# Sensors.net
KiCad netlist of a schematic drawn in Altium Designer
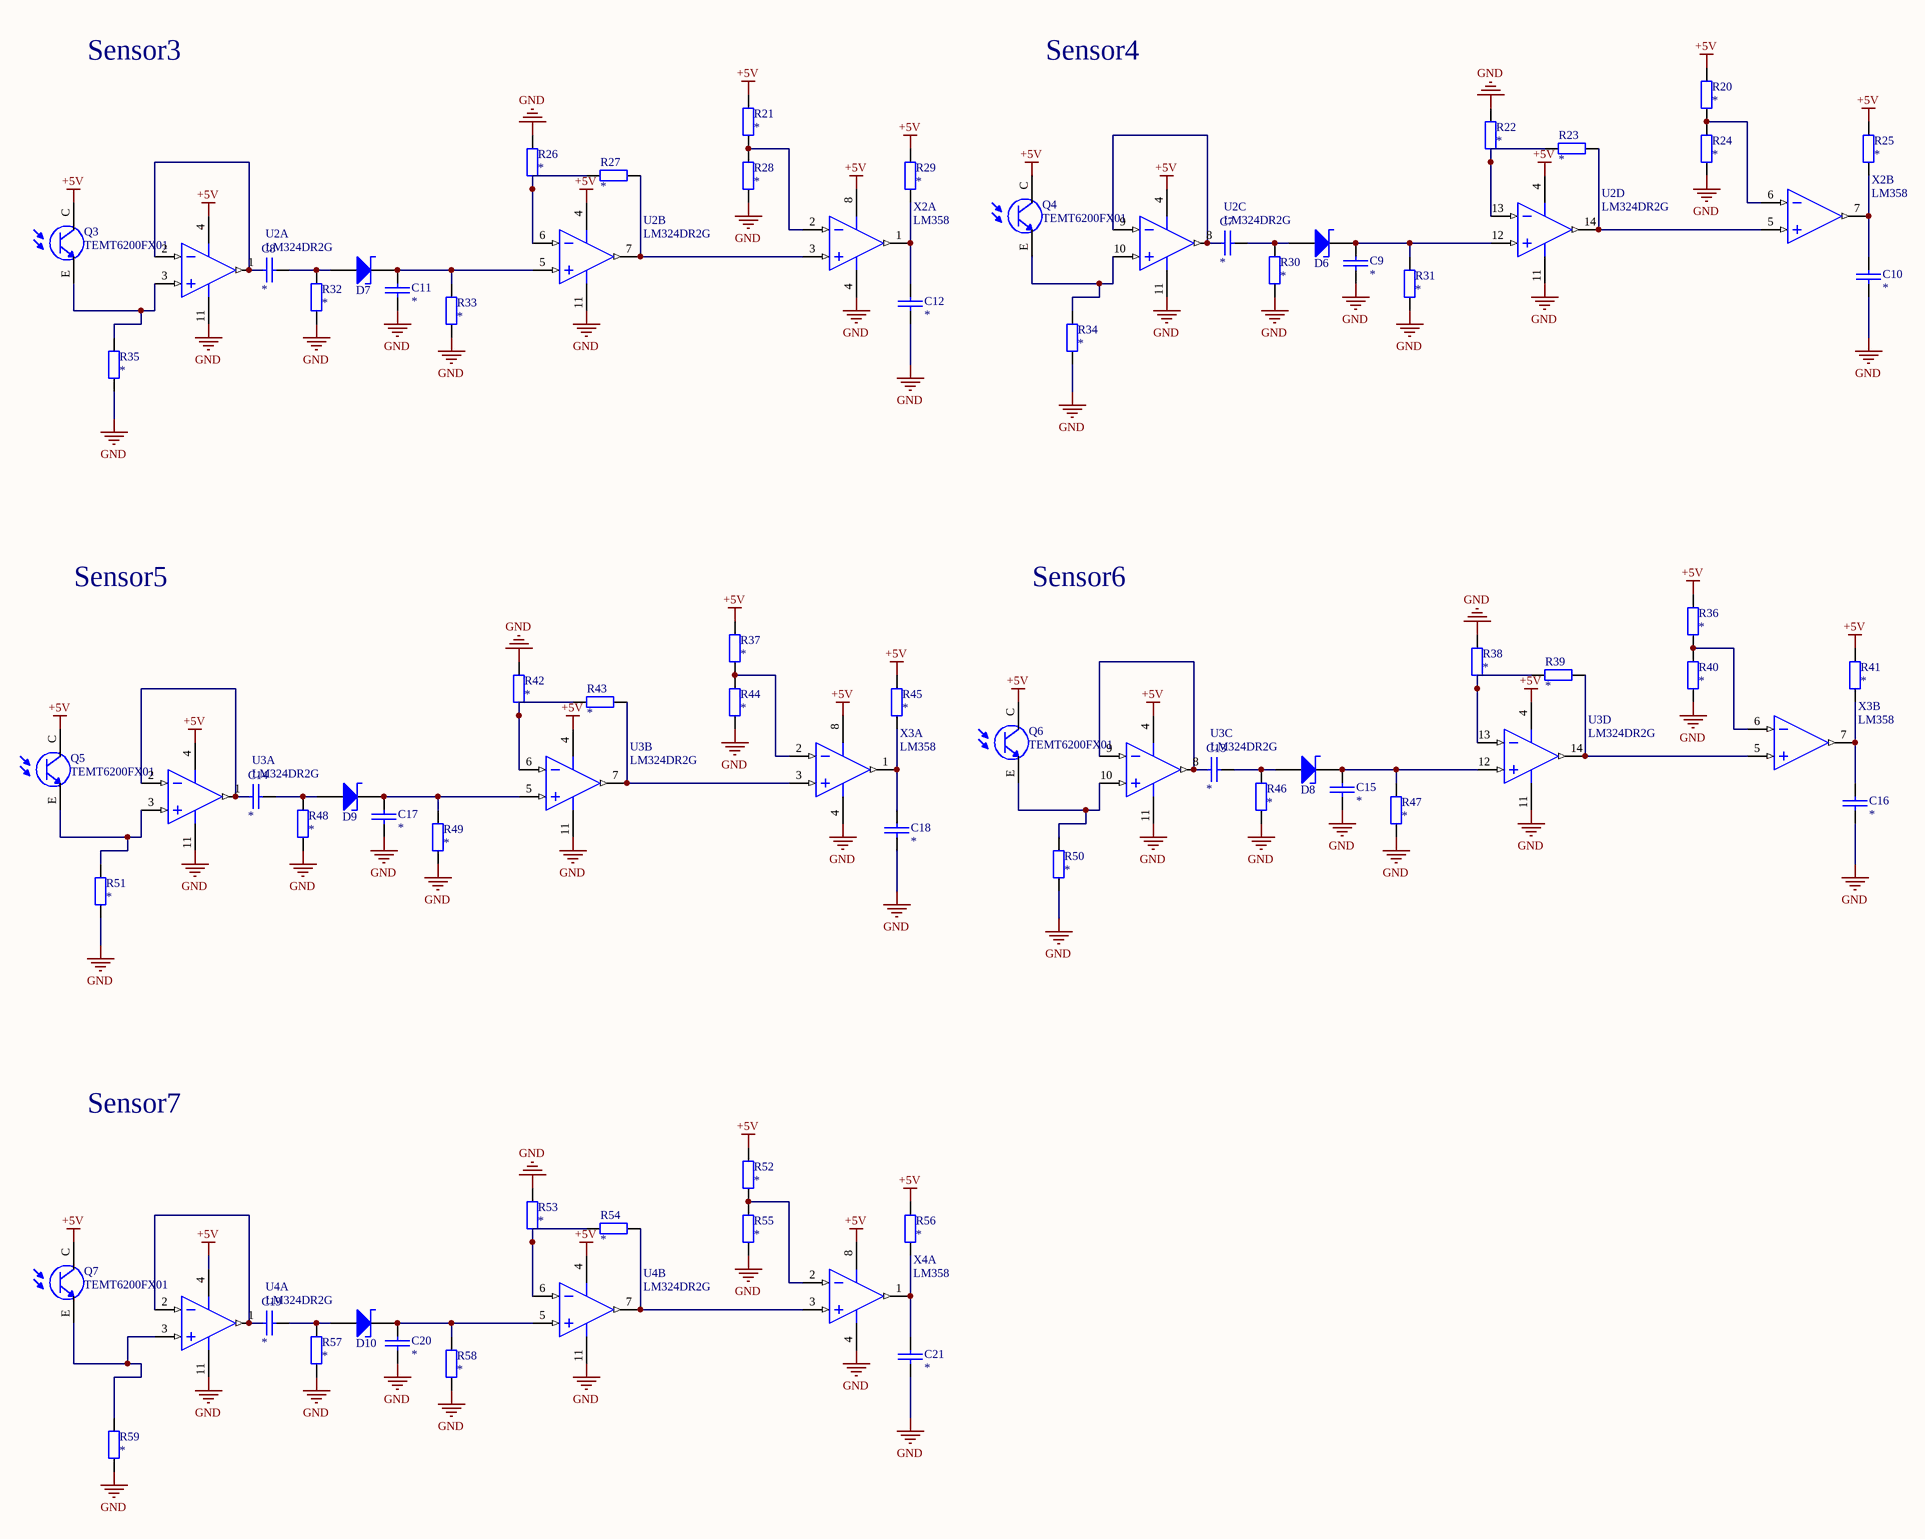
[diagram p0: Sensors.SchDoc]

(export (version "E")
  (design (tool "Eeschema 10.0.6"))
  (components
    (comp (ref "C7")
      (value "*")
      (footprint "0805 CAP")
      (description "SMT ceramic capacitor 0805 size")
      (libsource (lib "EE209_Library") (part "CerCap_SMT_0805"))
    )
    (comp (ref "C8")
      (value "*")
      (footprint "0805 CAP")
      (description "SMT ceramic capacitor 0805 size")
      (libsource (lib "EE209_Library") (part "CerCap_SMT_0805"))
    )
    (comp (ref "C9")
      (value "*")
      (footprint "0805 CAP")
      (description "SMT ceramic capacitor 0805 size")
      (libsource (lib "EE209_Library") (part "CerCap_SMT_0805"))
    )
    (comp (ref "C10")
      (value "*")
      (footprint "0805 CAP")
      (description "SMT ceramic capacitor 0805 size")
      (libsource (lib "EE209_Library") (part "CerCap_SMT_0805"))
    )
    (comp (ref "C11")
      (value "*")
      (footprint "0805 CAP")
      (description "SMT ceramic capacitor 0805 size")
      (libsource (lib "EE209_Library") (part "CerCap_SMT_0805"))
    )
    (comp (ref "C12")
      (value "*")
      (footprint "0805 CAP")
      (description "SMT ceramic capacitor 0805 size")
      (libsource (lib "EE209_Library") (part "CerCap_SMT_0805"))
    )
    (comp (ref "C13")
      (value "*")
      (footprint "0805 CAP")
      (description "SMT ceramic capacitor 0805 size")
      (libsource (lib "EE209_Library") (part "CerCap_SMT_0805"))
    )
    (comp (ref "C14")
      (value "*")
      (footprint "0805 CAP")
      (description "SMT ceramic capacitor 0805 size")
      (libsource (lib "EE209_Library") (part "CerCap_SMT_0805"))
    )
    (comp (ref "C15")
      (value "*")
      (footprint "0805 CAP")
      (description "SMT ceramic capacitor 0805 size")
      (libsource (lib "EE209_Library") (part "CerCap_SMT_0805"))
    )
    (comp (ref "C16")
      (value "*")
      (footprint "0805 CAP")
      (description "SMT ceramic capacitor 0805 size")
      (libsource (lib "EE209_Library") (part "CerCap_SMT_0805"))
    )
    (comp (ref "C17")
      (value "*")
      (footprint "0805 CAP")
      (description "SMT ceramic capacitor 0805 size")
      (libsource (lib "EE209_Library") (part "CerCap_SMT_0805"))
    )
    (comp (ref "C18")
      (value "*")
      (footprint "0805 CAP")
      (description "SMT ceramic capacitor 0805 size")
      (libsource (lib "EE209_Library") (part "CerCap_SMT_0805"))
    )
    (comp (ref "C19")
      (value "*")
      (footprint "0805 CAP")
      (description "SMT ceramic capacitor 0805 size")
      (libsource (lib "EE209_Library") (part "CerCap_SMT_0805"))
    )
    (comp (ref "C20")
      (value "*")
      (footprint "0805 CAP")
      (description "SMT ceramic capacitor 0805 size")
      (libsource (lib "EE209_Library") (part "CerCap_SMT_0805"))
    )
    (comp (ref "C21")
      (value "*")
      (footprint "0805 CAP")
      (description "SMT ceramic capacitor 0805 size")
      (libsource (lib "EE209_Library") (part "CerCap_SMT_0805"))
    )
    (comp (ref "D6")
      (value "BZT52H-B4V7")
      (footprint "SOD123")
      (description "SMT zener diode with SOD123 package")
      (fields
        (field (name "MANUFACTURER") "Nexperia USA Inc.")
        (field (name "MANUFACTURER PART NUMBER") "BZT52H-B4V7,115")
      )
      (libsource (lib "EE209_Library") (part "Zener_SMT_SOD123"))
    )
    (comp (ref "D7")
      (value "BZT52H-B4V7")
      (footprint "SOD123")
      (description "SMT zener diode with SOD123 package")
      (fields
        (field (name "MANUFACTURER") "Nexperia USA Inc.")
        (field (name "MANUFACTURER PART NUMBER") "BZT52H-B4V7,115")
      )
      (libsource (lib "EE209_Library") (part "Zener_SMT_SOD123"))
    )
    (comp (ref "D8")
      (value "BZT52H-B4V7")
      (footprint "SOD123")
      (description "SMT zener diode with SOD123 package")
      (fields
        (field (name "MANUFACTURER") "Nexperia USA Inc.")
        (field (name "MANUFACTURER PART NUMBER") "BZT52H-B4V7,115")
      )
      (libsource (lib "EE209_Library") (part "Zener_SMT_SOD123"))
    )
    (comp (ref "D9")
      (value "BZT52H-B4V7")
      (footprint "SOD123")
      (description "SMT zener diode with SOD123 package")
      (fields
        (field (name "MANUFACTURER") "Nexperia USA Inc.")
        (field (name "MANUFACTURER PART NUMBER") "BZT52H-B4V7,115")
      )
      (libsource (lib "EE209_Library") (part "Zener_SMT_SOD123"))
    )
    (comp (ref "D10")
      (value "BZT52H-B4V7")
      (footprint "SOD123")
      (description "SMT zener diode with SOD123 package")
      (fields
        (field (name "MANUFACTURER") "Nexperia USA Inc.")
        (field (name "MANUFACTURER PART NUMBER") "BZT52H-B4V7,115")
      )
      (libsource (lib "EE209_Library") (part "Zener_SMT_SOD123"))
    )
    (comp (ref "Q3")
      (value "TEMT6200FX01")
      (footprint "XDCR_TEMT6200FX01")
      (description "Phototransistors 550nm Top View 0805 (2012 Metric)")
      (fields (field (name "MF") "Vishay Semiconductor"))
      (libsource (lib "TEMT6200FX01") (part "TEMT6200FX01"))
    )
    (comp (ref "Q4")
      (value "TEMT6200FX01")
      (footprint "XDCR_TEMT6200FX01")
      (description "Phototransistors 550nm Top View 0805 (2012 Metric)")
      (fields (field (name "MF") "Vishay Semiconductor"))
      (libsource (lib "TEMT6200FX01") (part "TEMT6200FX01"))
    )
    (comp (ref "Q5")
      (value "TEMT6200FX01")
      (footprint "XDCR_TEMT6200FX01")
      (description "Phototransistors 550nm Top View 0805 (2012 Metric)")
      (fields (field (name "MF") "Vishay Semiconductor"))
      (libsource (lib "TEMT6200FX01") (part "TEMT6200FX01"))
    )
    (comp (ref "Q6")
      (value "TEMT6200FX01")
      (footprint "XDCR_TEMT6200FX01")
      (description "Phototransistors 550nm Top View 0805 (2012 Metric)")
      (fields (field (name "MF") "Vishay Semiconductor"))
      (libsource (lib "TEMT6200FX01") (part "TEMT6200FX01"))
    )
    (comp (ref "Q7")
      (value "TEMT6200FX01")
      (footprint "XDCR_TEMT6200FX01")
      (description "Phototransistors 550nm Top View 0805 (2012 Metric)")
      (fields (field (name "MF") "Vishay Semiconductor"))
      (libsource (lib "TEMT6200FX01") (part "TEMT6200FX01"))
    )
    (comp (ref "R20")
      (value "*")
      (footprint "0805 RES")
      (description "0805 resistor")
      (fields (field (name "PUBLISHER") "Altium Limited"))
      (libsource (lib "EE209_Library") (part "Res_SMT_0805"))
    )
    (comp (ref "R21")
      (value "*")
      (footprint "0805 RES")
      (description "0805 resistor")
      (fields (field (name "PUBLISHER") "Altium Limited"))
      (libsource (lib "EE209_Library") (part "Res_SMT_0805"))
    )
    (comp (ref "R22")
      (value "*")
      (footprint "0805 RES")
      (description "0805 resistor")
      (fields (field (name "PUBLISHER") "Altium Limited"))
      (libsource (lib "") (part "Res_SMT_0805_1"))
    )
    (comp (ref "R23")
      (value "*")
      (footprint "0805 RES")
      (description "0805 resistor")
      (fields (field (name "PUBLISHER") "Altium Limited"))
      (libsource (lib "") (part "Res_SMT_0805_2"))
    )
    (comp (ref "R24")
      (value "*")
      (footprint "0805 RES")
      (description "0805 resistor")
      (fields (field (name "PUBLISHER") "Altium Limited"))
      (libsource (lib "EE209_Library") (part "Res_SMT_0805"))
    )
    (comp (ref "R25")
      (value "*")
      (footprint "0805 RES")
      (description "0805 resistor")
      (fields (field (name "PUBLISHER") "Altium Limited"))
      (libsource (lib "EE209_Library") (part "Res_SMT_0805"))
    )
    (comp (ref "R26")
      (value "*")
      (footprint "0805 RES")
      (description "0805 resistor")
      (fields (field (name "PUBLISHER") "Altium Limited"))
      (libsource (lib "") (part "Res_SMT_0805_1"))
    )
    (comp (ref "R27")
      (value "*")
      (footprint "0805 RES")
      (description "0805 resistor")
      (fields (field (name "PUBLISHER") "Altium Limited"))
      (libsource (lib "") (part "Res_SMT_0805_2"))
    )
    (comp (ref "R28")
      (value "*")
      (footprint "0805 RES")
      (description "0805 resistor")
      (fields (field (name "PUBLISHER") "Altium Limited"))
      (libsource (lib "EE209_Library") (part "Res_SMT_0805"))
    )
    (comp (ref "R29")
      (value "*")
      (footprint "0805 RES")
      (description "0805 resistor")
      (fields (field (name "PUBLISHER") "Altium Limited"))
      (libsource (lib "EE209_Library") (part "Res_SMT_0805"))
    )
    (comp (ref "R30")
      (value "*")
      (footprint "0805 RES")
      (description "0805 resistor")
      (fields (field (name "PUBLISHER") "Altium Limited"))
      (libsource (lib "") (part "Res_SMT_0805_1"))
    )
    (comp (ref "R31")
      (value "*")
      (footprint "0805 RES")
      (description "0805 resistor")
      (fields (field (name "PUBLISHER") "Altium Limited"))
      (libsource (lib "") (part "Res_SMT_0805_1"))
    )
    (comp (ref "R32")
      (value "*")
      (footprint "0805 RES")
      (description "0805 resistor")
      (fields (field (name "PUBLISHER") "Altium Limited"))
      (libsource (lib "") (part "Res_SMT_0805_1"))
    )
    (comp (ref "R33")
      (value "*")
      (footprint "0805 RES")
      (description "0805 resistor")
      (fields (field (name "PUBLISHER") "Altium Limited"))
      (libsource (lib "") (part "Res_SMT_0805_1"))
    )
    (comp (ref "R34")
      (value "*")
      (footprint "0805 RES")
      (description "0805 resistor")
      (fields (field (name "PUBLISHER") "Altium Limited"))
      (libsource (lib "") (part "Res_SMT_0805_1"))
    )
    (comp (ref "R35")
      (value "*")
      (footprint "0805 RES")
      (description "0805 resistor")
      (fields (field (name "PUBLISHER") "Altium Limited"))
      (libsource (lib "") (part "Res_SMT_0805_1"))
    )
    (comp (ref "R36")
      (value "*")
      (footprint "0805 RES")
      (description "0805 resistor")
      (fields (field (name "PUBLISHER") "Altium Limited"))
      (libsource (lib "EE209_Library") (part "Res_SMT_0805"))
    )
    (comp (ref "R37")
      (value "*")
      (footprint "0805 RES")
      (description "0805 resistor")
      (fields (field (name "PUBLISHER") "Altium Limited"))
      (libsource (lib "EE209_Library") (part "Res_SMT_0805"))
    )
    (comp (ref "R38")
      (value "*")
      (footprint "0805 RES")
      (description "0805 resistor")
      (fields (field (name "PUBLISHER") "Altium Limited"))
      (libsource (lib "") (part "Res_SMT_0805_1"))
    )
    (comp (ref "R39")
      (value "*")
      (footprint "0805 RES")
      (description "0805 resistor")
      (fields (field (name "PUBLISHER") "Altium Limited"))
      (libsource (lib "") (part "Res_SMT_0805_2"))
    )
    (comp (ref "R40")
      (value "*")
      (footprint "0805 RES")
      (description "0805 resistor")
      (fields (field (name "PUBLISHER") "Altium Limited"))
      (libsource (lib "EE209_Library") (part "Res_SMT_0805"))
    )
    (comp (ref "R41")
      (value "*")
      (footprint "0805 RES")
      (description "0805 resistor")
      (fields (field (name "PUBLISHER") "Altium Limited"))
      (libsource (lib "EE209_Library") (part "Res_SMT_0805"))
    )
    (comp (ref "R42")
      (value "*")
      (footprint "0805 RES")
      (description "0805 resistor")
      (fields (field (name "PUBLISHER") "Altium Limited"))
      (libsource (lib "") (part "Res_SMT_0805_1"))
    )
    (comp (ref "R43")
      (value "*")
      (footprint "0805 RES")
      (description "0805 resistor")
      (fields (field (name "PUBLISHER") "Altium Limited"))
      (libsource (lib "") (part "Res_SMT_0805_2"))
    )
    (comp (ref "R44")
      (value "*")
      (footprint "0805 RES")
      (description "0805 resistor")
      (fields (field (name "PUBLISHER") "Altium Limited"))
      (libsource (lib "EE209_Library") (part "Res_SMT_0805"))
    )
    (comp (ref "R45")
      (value "*")
      (footprint "0805 RES")
      (description "0805 resistor")
      (fields (field (name "PUBLISHER") "Altium Limited"))
      (libsource (lib "EE209_Library") (part "Res_SMT_0805"))
    )
    (comp (ref "R46")
      (value "*")
      (footprint "0805 RES")
      (description "0805 resistor")
      (fields (field (name "PUBLISHER") "Altium Limited"))
      (libsource (lib "") (part "Res_SMT_0805_1"))
    )
    (comp (ref "R47")
      (value "*")
      (footprint "0805 RES")
      (description "0805 resistor")
      (fields (field (name "PUBLISHER") "Altium Limited"))
      (libsource (lib "") (part "Res_SMT_0805_1"))
    )
    (comp (ref "R48")
      (value "*")
      (footprint "0805 RES")
      (description "0805 resistor")
      (fields (field (name "PUBLISHER") "Altium Limited"))
      (libsource (lib "") (part "Res_SMT_0805_1"))
    )
    (comp (ref "R49")
      (value "*")
      (footprint "0805 RES")
      (description "0805 resistor")
      (fields (field (name "PUBLISHER") "Altium Limited"))
      (libsource (lib "") (part "Res_SMT_0805_1"))
    )
    (comp (ref "R50")
      (value "*")
      (footprint "0805 RES")
      (description "0805 resistor")
      (fields (field (name "PUBLISHER") "Altium Limited"))
      (libsource (lib "") (part "Res_SMT_0805_1"))
    )
    (comp (ref "R51")
      (value "*")
      (footprint "0805 RES")
      (description "0805 resistor")
      (fields (field (name "PUBLISHER") "Altium Limited"))
      (libsource (lib "") (part "Res_SMT_0805_1"))
    )
    (comp (ref "R52")
      (value "*")
      (footprint "0805 RES")
      (description "0805 resistor")
      (fields (field (name "PUBLISHER") "Altium Limited"))
      (libsource (lib "EE209_Library") (part "Res_SMT_0805"))
    )
    (comp (ref "R53")
      (value "*")
      (footprint "0805 RES")
      (description "0805 resistor")
      (fields (field (name "PUBLISHER") "Altium Limited"))
      (libsource (lib "") (part "Res_SMT_0805_1"))
    )
    (comp (ref "R54")
      (value "*")
      (footprint "0805 RES")
      (description "0805 resistor")
      (fields (field (name "PUBLISHER") "Altium Limited"))
      (libsource (lib "") (part "Res_SMT_0805_2"))
    )
    (comp (ref "R55")
      (value "*")
      (footprint "0805 RES")
      (description "0805 resistor")
      (fields (field (name "PUBLISHER") "Altium Limited"))
      (libsource (lib "EE209_Library") (part "Res_SMT_0805"))
    )
    (comp (ref "R56")
      (value "*")
      (footprint "0805 RES")
      (description "0805 resistor")
      (fields (field (name "PUBLISHER") "Altium Limited"))
      (libsource (lib "EE209_Library") (part "Res_SMT_0805"))
    )
    (comp (ref "R57")
      (value "*")
      (footprint "0805 RES")
      (description "0805 resistor")
      (fields (field (name "PUBLISHER") "Altium Limited"))
      (libsource (lib "") (part "Res_SMT_0805_1"))
    )
    (comp (ref "R58")
      (value "*")
      (footprint "0805 RES")
      (description "0805 resistor")
      (fields (field (name "PUBLISHER") "Altium Limited"))
      (libsource (lib "") (part "Res_SMT_0805_1"))
    )
    (comp (ref "R59")
      (value "*")
      (footprint "0805 RES")
      (description "0805 resistor")
      (fields (field (name "PUBLISHER") "Altium Limited"))
      (libsource (lib "") (part "Res_SMT_0805_1"))
    )
    (comp (ref "U2")
      (value "LM324DR2G")
      (footprint "SOIC-14")
      (fields (field (name "MANUFACTURER") "On Semiconductor"))
      (libsource (lib "EE209_Library") (part "LM324DR_SMT_SOIC16"))
    )
    (comp (ref "U3")
      (value "LM324DR2G")
      (footprint "SOIC-14")
      (fields (field (name "MANUFACTURER") "On Semiconductor"))
      (libsource (lib "EE209_Library") (part "LM324DR_SMT_SOIC16"))
    )
    (comp (ref "U4")
      (value "LM324DR2G")
      (footprint "SOIC-14")
      (fields (field (name "MANUFACTURER") "On Semiconductor"))
      (libsource (lib "EE209_Library") (part "LM324DR_SMT_SOIC16"))
    )
    (comp (ref "X2")
      (value "LM358")
      (footprint "SO - 8")
      (description "IC OPAMP 8SOIC")
      (libsource (lib "EE209_Library") (part "LM358_SMT_SOIC8"))
    )
    (comp (ref "X3")
      (value "LM358")
      (footprint "SO - 8")
      (description "IC OPAMP 8SOIC")
      (libsource (lib "EE209_Library") (part "LM358_SMT_SOIC8"))
    )
    (comp (ref "X4")
      (value "LM358")
      (footprint "SO - 8")
      (description "IC OPAMP 8SOIC")
      (libsource (lib "EE209_Library") (part "LM358_SMT_SOIC8"))
    )
  )
  (nets
    (net (code "1") (name "+5V") (class "Default")
      (node (ref "Q3") (pin "C") (pinfunction "C_C") (pintype "passive"))
      (node (ref "Q4") (pin "C") (pinfunction "C_C") (pintype "passive"))
      (node (ref "Q5") (pin "C") (pinfunction "C_C") (pintype "passive"))
      (node (ref "Q6") (pin "C") (pinfunction "C_C") (pintype "passive"))
      (node (ref "Q7") (pin "C") (pinfunction "C_C") (pintype "passive"))
      (node (ref "R20") (pin "1") (pinfunction "1_1") (pintype "passive"))
      (node (ref "R21") (pin "1") (pinfunction "1_1") (pintype "passive"))
      (node (ref "R25") (pin "1") (pinfunction "1_1") (pintype "passive"))
      (node (ref "R29") (pin "1") (pinfunction "1_1") (pintype "passive"))
      (node (ref "R36") (pin "1") (pinfunction "1_1") (pintype "passive"))
      (node (ref "R37") (pin "1") (pinfunction "1_1") (pintype "passive"))
      (node (ref "R41") (pin "1") (pinfunction "1_1") (pintype "passive"))
      (node (ref "R45") (pin "1") (pinfunction "1_1") (pintype "passive"))
      (node (ref "R52") (pin "1") (pinfunction "1_1") (pintype "passive"))
      (node (ref "R56") (pin "1") (pinfunction "1_1") (pintype "passive"))
      (node (ref "U2") (pin "4") (pinfunction "VCC_4") (pintype "power_in"))
      (node (ref "U3") (pin "4") (pinfunction "VCC_4") (pintype "power_in"))
      (node (ref "U4") (pin "4") (pinfunction "VCC_4") (pintype "power_in"))
      (node (ref "X2") (pin "8") (pinfunction "VDD_8") (pintype "power_in"))
      (node (ref "X3") (pin "8") (pinfunction "VDD_8") (pintype "power_in"))
      (node (ref "X4") (pin "8") (pinfunction "VDD_8") (pintype "power_in"))
    )
    (net (code "2") (name "GND") (class "Default")
      (node (ref "C10") (pin "2") (pinfunction "2_2") (pintype "passive"))
      (node (ref "C11") (pin "2") (pinfunction "2_2") (pintype "passive"))
      (node (ref "C12") (pin "2") (pinfunction "2_2") (pintype "passive"))
      (node (ref "C15") (pin "2") (pinfunction "2_2") (pintype "passive"))
      (node (ref "C16") (pin "2") (pinfunction "2_2") (pintype "passive"))
      (node (ref "C17") (pin "2") (pinfunction "2_2") (pintype "passive"))
      (node (ref "C18") (pin "2") (pinfunction "2_2") (pintype "passive"))
      (node (ref "C20") (pin "2") (pinfunction "2_2") (pintype "passive"))
      (node (ref "C21") (pin "2") (pinfunction "2_2") (pintype "passive"))
      (node (ref "C9") (pin "2") (pinfunction "2_2") (pintype "passive"))
      (node (ref "R22") (pin "2") (pinfunction "2_2") (pintype "passive"))
      (node (ref "R24") (pin "2") (pinfunction "2_2") (pintype "passive"))
      (node (ref "R26") (pin "2") (pinfunction "2_2") (pintype "passive"))
      (node (ref "R28") (pin "2") (pinfunction "2_2") (pintype "passive"))
      (node (ref "R30") (pin "1") (pinfunction "1_1") (pintype "passive"))
      (node (ref "R31") (pin "1") (pinfunction "1_1") (pintype "passive"))
      (node (ref "R32") (pin "1") (pinfunction "1_1") (pintype "passive"))
      (node (ref "R33") (pin "1") (pinfunction "1_1") (pintype "passive"))
      (node (ref "R34") (pin "1") (pinfunction "1_1") (pintype "passive"))
      (node (ref "R35") (pin "1") (pinfunction "1_1") (pintype "passive"))
      (node (ref "R38") (pin "2") (pinfunction "2_2") (pintype "passive"))
      (node (ref "R40") (pin "2") (pinfunction "2_2") (pintype "passive"))
      (node (ref "R42") (pin "2") (pinfunction "2_2") (pintype "passive"))
      (node (ref "R44") (pin "2") (pinfunction "2_2") (pintype "passive"))
      (node (ref "R46") (pin "1") (pinfunction "1_1") (pintype "passive"))
      (node (ref "R47") (pin "1") (pinfunction "1_1") (pintype "passive"))
      (node (ref "R48") (pin "1") (pinfunction "1_1") (pintype "passive"))
      (node (ref "R49") (pin "1") (pinfunction "1_1") (pintype "passive"))
      (node (ref "R50") (pin "1") (pinfunction "1_1") (pintype "passive"))
      (node (ref "R51") (pin "1") (pinfunction "1_1") (pintype "passive"))
      (node (ref "R53") (pin "2") (pinfunction "2_2") (pintype "passive"))
      (node (ref "R55") (pin "2") (pinfunction "2_2") (pintype "passive"))
      (node (ref "R57") (pin "1") (pinfunction "1_1") (pintype "passive"))
      (node (ref "R58") (pin "1") (pinfunction "1_1") (pintype "passive"))
      (node (ref "R59") (pin "1") (pinfunction "1_1") (pintype "passive"))
      (node (ref "U2") (pin "11") (pinfunction "VEE/GND_11") (pintype "power_in"))
      (node (ref "U3") (pin "11") (pinfunction "VEE/GND_11") (pintype "power_in"))
      (node (ref "U4") (pin "11") (pinfunction "VEE/GND_11") (pintype "power_in"))
      (node (ref "X2") (pin "4") (pinfunction "VSS_4") (pintype "power_in"))
      (node (ref "X3") (pin "4") (pinfunction "VSS_4") (pintype "power_in"))
      (node (ref "X4") (pin "4") (pinfunction "VSS_4") (pintype "power_in"))
    )
    (net (code "3") (name "Net-(D6-A)") (class "Default")
      (node (ref "C7") (pin "2") (pinfunction "2_2") (pintype "passive"))
      (node (ref "D6") (pin "1") (pinfunction "A_1") (pintype "passive"))
      (node (ref "R30") (pin "2") (pinfunction "2_2") (pintype "passive"))
    )
    (net (code "4") (name "Net-(D6-K)") (class "Default")
      (node (ref "C9") (pin "1") (pinfunction "1_1") (pintype "passive"))
      (node (ref "D6") (pin "2") (pinfunction "K_2") (pintype "passive"))
      (node (ref "R31") (pin "2") (pinfunction "2_2") (pintype "passive"))
      (node (ref "U2") (pin "12") (pinfunction "IN4+_12") (pintype "input"))
    )
    (net (code "5") (name "Net-(D7-A)") (class "Default")
      (node (ref "C8") (pin "2") (pinfunction "2_2") (pintype "passive"))
      (node (ref "D7") (pin "1") (pinfunction "A_1") (pintype "passive"))
      (node (ref "R32") (pin "2") (pinfunction "2_2") (pintype "passive"))
    )
    (net (code "6") (name "Net-(D7-K)") (class "Default")
      (node (ref "C11") (pin "1") (pinfunction "1_1") (pintype "passive"))
      (node (ref "D7") (pin "2") (pinfunction "K_2") (pintype "passive"))
      (node (ref "R33") (pin "2") (pinfunction "2_2") (pintype "passive"))
      (node (ref "U2") (pin "5") (pinfunction "IN2+_5") (pintype "input"))
    )
    (net (code "7") (name "Net-(D8-A)") (class "Default")
      (node (ref "C13") (pin "2") (pinfunction "2_2") (pintype "passive"))
      (node (ref "D8") (pin "1") (pinfunction "A_1") (pintype "passive"))
      (node (ref "R46") (pin "2") (pinfunction "2_2") (pintype "passive"))
    )
    (net (code "8") (name "Net-(D8-K)") (class "Default")
      (node (ref "C15") (pin "1") (pinfunction "1_1") (pintype "passive"))
      (node (ref "D8") (pin "2") (pinfunction "K_2") (pintype "passive"))
      (node (ref "R47") (pin "2") (pinfunction "2_2") (pintype "passive"))
      (node (ref "U3") (pin "12") (pinfunction "IN4+_12") (pintype "input"))
    )
    (net (code "9") (name "Net-(D9-A)") (class "Default")
      (node (ref "C14") (pin "2") (pinfunction "2_2") (pintype "passive"))
      (node (ref "D9") (pin "1") (pinfunction "A_1") (pintype "passive"))
      (node (ref "R48") (pin "2") (pinfunction "2_2") (pintype "passive"))
    )
    (net (code "10") (name "Net-(D9-K)") (class "Default")
      (node (ref "C17") (pin "1") (pinfunction "1_1") (pintype "passive"))
      (node (ref "D9") (pin "2") (pinfunction "K_2") (pintype "passive"))
      (node (ref "R49") (pin "2") (pinfunction "2_2") (pintype "passive"))
      (node (ref "U3") (pin "5") (pinfunction "IN2+_5") (pintype "input"))
    )
    (net (code "11") (name "Net-(D10-A)") (class "Default")
      (node (ref "C19") (pin "2") (pinfunction "2_2") (pintype "passive"))
      (node (ref "D10") (pin "1") (pinfunction "A_1") (pintype "passive"))
      (node (ref "R57") (pin "2") (pinfunction "2_2") (pintype "passive"))
    )
    (net (code "12") (name "Net-(D10-K)") (class "Default")
      (node (ref "C20") (pin "1") (pinfunction "1_1") (pintype "passive"))
      (node (ref "D10") (pin "2") (pinfunction "K_2") (pintype "passive"))
      (node (ref "R58") (pin "2") (pinfunction "2_2") (pintype "passive"))
      (node (ref "U4") (pin "5") (pinfunction "IN2+_5") (pintype "input"))
    )
    (net (code "13") (name "Net-(U2A-IN1+)") (class "Default")
      (node (ref "Q3") (pin "E") (pinfunction "E_E") (pintype "passive"))
      (node (ref "R35") (pin "2") (pinfunction "2_2") (pintype "passive"))
      (node (ref "U2") (pin "3") (pinfunction "IN1+_3") (pintype "input"))
    )
    (net (code "14") (name "Net-(U2A-IN1-)") (class "Default")
      (node (ref "C8") (pin "1") (pinfunction "1_1") (pintype "passive"))
      (node (ref "U2") (pin "1") (pinfunction "OUT1_1") (pintype "output"))
      (node (ref "U2") (pin "2") (pinfunction "IN1-_2") (pintype "input"))
    )
    (net (code "15") (name "Net-(U2B-IN2-)") (class "Default")
      (node (ref "R26") (pin "1") (pinfunction "1_1") (pintype "passive"))
      (node (ref "R27") (pin "2") (pinfunction "2_2") (pintype "passive"))
      (node (ref "U2") (pin "6") (pinfunction "IN2-_6") (pintype "input"))
    )
    (net (code "16") (name "Net-(U2B-OUT2)") (class "Default")
      (node (ref "R27") (pin "1") (pinfunction "1_1") (pintype "passive"))
      (node (ref "U2") (pin "7") (pinfunction "OUT2_7") (pintype "output"))
      (node (ref "X2") (pin "3") (pinfunction "VINA+_3") (pintype "input"))
    )
    (net (code "17") (name "Net-(U2C-IN3+)") (class "Default")
      (node (ref "Q4") (pin "E") (pinfunction "E_E") (pintype "passive"))
      (node (ref "R34") (pin "2") (pinfunction "2_2") (pintype "passive"))
      (node (ref "U2") (pin "10") (pinfunction "IN3+_10") (pintype "input"))
    )
    (net (code "18") (name "Net-(U2C-IN3-)") (class "Default")
      (node (ref "C7") (pin "1") (pinfunction "1_1") (pintype "passive"))
      (node (ref "U2") (pin "8") (pinfunction "OUT3_8") (pintype "output"))
      (node (ref "U2") (pin "9") (pinfunction "IN3-_9") (pintype "input"))
    )
    (net (code "19") (name "Net-(U2D-IN4-)") (class "Default")
      (node (ref "R22") (pin "1") (pinfunction "1_1") (pintype "passive"))
      (node (ref "R23") (pin "2") (pinfunction "2_2") (pintype "passive"))
      (node (ref "U2") (pin "13") (pinfunction "IN4-_13") (pintype "input"))
    )
    (net (code "20") (name "Net-(U2D-OUT4)") (class "Default")
      (node (ref "R23") (pin "1") (pinfunction "1_1") (pintype "passive"))
      (node (ref "U2") (pin "14") (pinfunction "OUT4_14") (pintype "output"))
      (node (ref "X2") (pin "5") (pinfunction "VINA+_5") (pintype "input"))
    )
    (net (code "21") (name "Net-(U3A-IN1+)") (class "Default")
      (node (ref "Q5") (pin "E") (pinfunction "E_E") (pintype "passive"))
      (node (ref "R51") (pin "2") (pinfunction "2_2") (pintype "passive"))
      (node (ref "U3") (pin "3") (pinfunction "IN1+_3") (pintype "input"))
    )
    (net (code "22") (name "Net-(U3A-IN1-)") (class "Default")
      (node (ref "C14") (pin "1") (pinfunction "1_1") (pintype "passive"))
      (node (ref "U3") (pin "1") (pinfunction "OUT1_1") (pintype "output"))
      (node (ref "U3") (pin "2") (pinfunction "IN1-_2") (pintype "input"))
    )
    (net (code "23") (name "Net-(U3B-IN2-)") (class "Default")
      (node (ref "R42") (pin "1") (pinfunction "1_1") (pintype "passive"))
      (node (ref "R43") (pin "2") (pinfunction "2_2") (pintype "passive"))
      (node (ref "U3") (pin "6") (pinfunction "IN2-_6") (pintype "input"))
    )
    (net (code "24") (name "Net-(U3B-OUT2)") (class "Default")
      (node (ref "R43") (pin "1") (pinfunction "1_1") (pintype "passive"))
      (node (ref "U3") (pin "7") (pinfunction "OUT2_7") (pintype "output"))
      (node (ref "X3") (pin "3") (pinfunction "VINA+_3") (pintype "input"))
    )
    (net (code "25") (name "Net-(U3C-IN3+)") (class "Default")
      (node (ref "Q6") (pin "E") (pinfunction "E_E") (pintype "passive"))
      (node (ref "R50") (pin "2") (pinfunction "2_2") (pintype "passive"))
      (node (ref "U3") (pin "10") (pinfunction "IN3+_10") (pintype "input"))
    )
    (net (code "26") (name "Net-(U3C-IN3-)") (class "Default")
      (node (ref "C13") (pin "1") (pinfunction "1_1") (pintype "passive"))
      (node (ref "U3") (pin "8") (pinfunction "OUT3_8") (pintype "output"))
      (node (ref "U3") (pin "9") (pinfunction "IN3-_9") (pintype "input"))
    )
    (net (code "27") (name "Net-(U3D-IN4-)") (class "Default")
      (node (ref "R38") (pin "1") (pinfunction "1_1") (pintype "passive"))
      (node (ref "R39") (pin "2") (pinfunction "2_2") (pintype "passive"))
      (node (ref "U3") (pin "13") (pinfunction "IN4-_13") (pintype "input"))
    )
    (net (code "28") (name "Net-(U3D-OUT4)") (class "Default")
      (node (ref "R39") (pin "1") (pinfunction "1_1") (pintype "passive"))
      (node (ref "U3") (pin "14") (pinfunction "OUT4_14") (pintype "output"))
      (node (ref "X3") (pin "5") (pinfunction "VINA+_5") (pintype "input"))
    )
    (net (code "29") (name "Net-(U4A-IN1+)") (class "Default")
      (node (ref "Q7") (pin "E") (pinfunction "E_E") (pintype "passive"))
      (node (ref "R59") (pin "2") (pinfunction "2_2") (pintype "passive"))
      (node (ref "U4") (pin "3") (pinfunction "IN1+_3") (pintype "input"))
    )
    (net (code "30") (name "Net-(U4A-IN1-)") (class "Default")
      (node (ref "C19") (pin "1") (pinfunction "1_1") (pintype "passive"))
      (node (ref "U4") (pin "1") (pinfunction "OUT1_1") (pintype "output"))
      (node (ref "U4") (pin "2") (pinfunction "IN1-_2") (pintype "input"))
    )
    (net (code "31") (name "Net-(U4B-IN2-)") (class "Default")
      (node (ref "R53") (pin "1") (pinfunction "1_1") (pintype "passive"))
      (node (ref "R54") (pin "2") (pinfunction "2_2") (pintype "passive"))
      (node (ref "U4") (pin "6") (pinfunction "IN2-_6") (pintype "input"))
    )
    (net (code "32") (name "Net-(U4B-OUT2)") (class "Default")
      (node (ref "R54") (pin "1") (pinfunction "1_1") (pintype "passive"))
      (node (ref "U4") (pin "7") (pinfunction "OUT2_7") (pintype "output"))
      (node (ref "X4") (pin "3") (pinfunction "VINA+_3") (pintype "input"))
    )
    (net (code "33") (name "Net-(X2A-VINA-)") (class "Default")
      (node (ref "R21") (pin "2") (pinfunction "2_2") (pintype "passive"))
      (node (ref "R28") (pin "1") (pinfunction "1_1") (pintype "passive"))
      (node (ref "X2") (pin "2") (pinfunction "VINA-_2") (pintype "input"))
    )
    (net (code "34") (name "Net-(X2A-VOUTA)") (class "Default")
      (node (ref "C12") (pin "1") (pinfunction "1_1") (pintype "passive"))
      (node (ref "R29") (pin "2") (pinfunction "2_2") (pintype "passive"))
      (node (ref "X2") (pin "1") (pinfunction "VOUTA_1") (pintype "output"))
    )
    (net (code "35") (name "Net-(X2B-VINA-)") (class "Default")
      (node (ref "R20") (pin "2") (pinfunction "2_2") (pintype "passive"))
      (node (ref "R24") (pin "1") (pinfunction "1_1") (pintype "passive"))
      (node (ref "X2") (pin "6") (pinfunction "VINA-_6") (pintype "input"))
    )
    (net (code "36") (name "Net-(X2B-VOUTA)") (class "Default")
      (node (ref "C10") (pin "1") (pinfunction "1_1") (pintype "passive"))
      (node (ref "R25") (pin "2") (pinfunction "2_2") (pintype "passive"))
      (node (ref "X2") (pin "7") (pinfunction "VOUTA_7") (pintype "output"))
    )
    (net (code "37") (name "Net-(X3A-VINA-)") (class "Default")
      (node (ref "R37") (pin "2") (pinfunction "2_2") (pintype "passive"))
      (node (ref "R44") (pin "1") (pinfunction "1_1") (pintype "passive"))
      (node (ref "X3") (pin "2") (pinfunction "VINA-_2") (pintype "input"))
    )
    (net (code "38") (name "Net-(X3A-VOUTA)") (class "Default")
      (node (ref "C18") (pin "1") (pinfunction "1_1") (pintype "passive"))
      (node (ref "R45") (pin "2") (pinfunction "2_2") (pintype "passive"))
      (node (ref "X3") (pin "1") (pinfunction "VOUTA_1") (pintype "output"))
    )
    (net (code "39") (name "Net-(X3B-VINA-)") (class "Default")
      (node (ref "R36") (pin "2") (pinfunction "2_2") (pintype "passive"))
      (node (ref "R40") (pin "1") (pinfunction "1_1") (pintype "passive"))
      (node (ref "X3") (pin "6") (pinfunction "VINA-_6") (pintype "input"))
    )
    (net (code "40") (name "Net-(X3B-VOUTA)") (class "Default")
      (node (ref "C16") (pin "1") (pinfunction "1_1") (pintype "passive"))
      (node (ref "R41") (pin "2") (pinfunction "2_2") (pintype "passive"))
      (node (ref "X3") (pin "7") (pinfunction "VOUTA_7") (pintype "output"))
    )
    (net (code "41") (name "Net-(X4A-VINA-)") (class "Default")
      (node (ref "R52") (pin "2") (pinfunction "2_2") (pintype "passive"))
      (node (ref "R55") (pin "1") (pinfunction "1_1") (pintype "passive"))
      (node (ref "X4") (pin "2") (pinfunction "VINA-_2") (pintype "input"))
    )
    (net (code "42") (name "Net-(X4A-VOUTA)") (class "Default")
      (node (ref "C21") (pin "1") (pinfunction "1_1") (pintype "passive"))
      (node (ref "R56") (pin "2") (pinfunction "2_2") (pintype "passive"))
      (node (ref "X4") (pin "1") (pinfunction "VOUTA_1") (pintype "output"))
    )
  )
)
